# IR.net
KiCad netlist of a schematic drawn in EAGLE
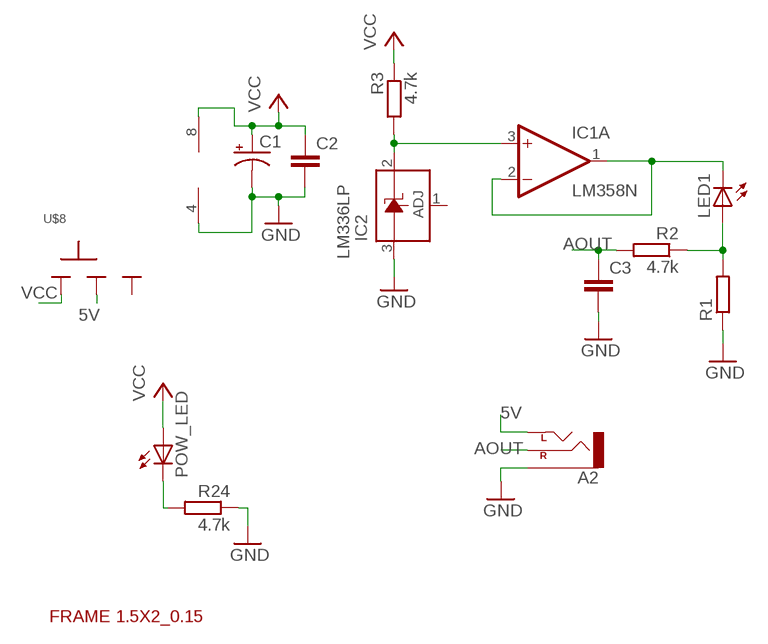
[diagram p0: schematic, sheet 1]

(export (version "E")
  (design (tool "Eeschema 10.0.6"))
  (components
    (comp (ref "A2")
      (value "AUX-CONNECTOR_CEDT_JANUARY_2015_V5_AUDIO-JACKPTH")
      (footprint "eagle-import:AUX-CONNECTOR_CEDT_JANUARY_2015_V5_AUDIO-JACK")
      (libsource (lib "eagle-import") (part "AUX-CONNECTOR_CEDT_JANUARY_2015_V5_AUDIO-JACKPTH"))
    )
    (comp (ref "C1")
      (value "CAP_POL")
      (footprint "eagle-import:E2,5-5-10U")
      (libsource (lib "eagle-import") (part "CAP_POL"))
    )
    (comp (ref "C2")
      (value "C-EU025-024X044")
      (footprint "eagle-import:C025-024X044")
      (libsource (lib "eagle-import") (part "C-EU025-024X044"))
    )
    (comp (ref "C3")
      (value "C-EU025-024X044")
      (footprint "eagle-import:C025-024X044")
      (libsource (lib "eagle-import") (part "C-EU025-024X044"))
    )
    (comp (ref "IC1")
      (value "LM358N")
      (footprint "eagle-import:DIL08")
      (libsource (lib "eagle-import") (part "LM358N"))
    )
    (comp (ref "IC2")
      (value "LM336LP")
      (footprint "eagle-import:TO92")
      (libsource (lib "eagle-import") (part "LM336LP"))
    )
    (comp (ref "LED1")
      (value "LED5MM")
      (footprint "eagle-import:LED5MM")
      (libsource (lib "eagle-import") (part "LED5MM"))
    )
    (comp (ref "POW_LED")
      (value "LED3MM")
      (footprint "eagle-import:LED3MM")
      (libsource (lib "eagle-import") (part "LED3MM"))
    )
    (comp (ref "R1")
      (value "R-EU_0204/7")
      (footprint "eagle-import:0204_7")
      (libsource (lib "eagle-import") (part "resistor_348_R-EU_0204/7"))
    )
    (comp (ref "R2")
      (value "4.7k")
      (footprint "eagle-import:0204_7")
      (libsource (lib "eagle-import") (part "R-EU_0204/7"))
    )
    (comp (ref "R3")
      (value "4.7k")
      (footprint "eagle-import:0204_7")
      (libsource (lib "eagle-import") (part "R-EU_0204/7"))
    )
    (comp (ref "R24")
      (value "4.7k")
      (footprint "eagle-import:0204_7")
      (libsource (lib "eagle-import") (part "R-EU_0204/7"))
    )
    (comp (ref "U$1")
      (value "FRAME_1.5X2_RAD_0.15")
      (footprint "eagle-import:FRAME_1.5X2_RAD_0.15")
      (libsource (lib "eagle-import") (part "FRAME_1.5X2_RAD_0.15"))
    )
    (comp (ref "U$8")
      (value "SLIDESWITCH-BIG")
      (footprint "eagle-import:BIGSWITCH")
      (libsource (lib "eagle-import") (part "SLIDESWITCH-BIG"))
    )
  )
  (nets
    (net (code "1") (name "/5V") (class "Default")
      (node (ref "A2") (pin "TIP") (pinfunction "LEFT_TIP") (pintype "bidirectional"))
      (node (ref "U$8") (pin "2") (pinfunction "2_2") (pintype "bidirectional"))
    )
    (net (code "2") (name "/AOUT") (class "Default")
      (node (ref "A2") (pin "RING") (pinfunction "RIGHT_RING") (pintype "bidirectional"))
      (node (ref "C3") (pin "1") (pinfunction "1_1") (pintype "passive"))
      (node (ref "R2") (pin "2") (pinfunction "2_2") (pintype "passive"))
    )
    (net (code "3") (name "GND") (class "Default")
      (node (ref "A2") (pin "SLEEVE") (pinfunction "SLEEVE_SLEEVE") (pintype "bidirectional"))
      (node (ref "C1") (pin "-") (pinfunction "-_-") (pintype "passive"))
      (node (ref "C2") (pin "2") (pinfunction "2_2") (pintype "passive"))
      (node (ref "C3") (pin "2") (pinfunction "2_2") (pintype "passive"))
      (node (ref "IC1") (pin "4") (pinfunction "V-_4") (pintype "power_in"))
      (node (ref "IC2") (pin "3") (pinfunction "A_3") (pintype "input"))
      (node (ref "R1") (pin "1") (pinfunction "1_1") (pintype "passive"))
      (node (ref "R24") (pin "1") (pinfunction "1_1") (pintype "passive"))
    )
    (net (code "4") (name "Net-(IC1A-+IN)") (class "Default")
      (node (ref "IC1") (pin "3") (pinfunction "+IN_3") (pintype "input"))
      (node (ref "IC2") (pin "2") (pinfunction "C_2") (pintype "passive"))
      (node (ref "R3") (pin "2") (pinfunction "2_2") (pintype "passive"))
    )
    (net (code "5") (name "Net-(IC1A--IN)") (class "Default")
      (node (ref "IC1") (pin "1") (pinfunction "OUT_1") (pintype "output"))
      (node (ref "IC1") (pin "2") (pinfunction "-IN_2") (pintype "input"))
      (node (ref "LED1") (pin "K") (pinfunction "C_K") (pintype "passive"))
    )
    (net (code "6") (name "Net-(LED1-PadA)") (class "Default")
      (node (ref "LED1") (pin "A") (pinfunction "A_A") (pintype "passive"))
      (node (ref "R1") (pin "2") (pinfunction "2_2") (pintype "passive"))
      (node (ref "R2") (pin "1") (pinfunction "1_1") (pintype "passive"))
    )
    (net (code "7") (name "Net-(POW_LED-C)") (class "Default")
      (node (ref "POW_LED") (pin "K") (pinfunction "C_K") (pintype "passive"))
      (node (ref "R24") (pin "2") (pinfunction "2_2") (pintype "passive"))
    )
    (net (code "8") (name "VCC") (class "Default")
      (node (ref "C1") (pin "+") (pinfunction "+_+") (pintype "passive"))
      (node (ref "C2") (pin "1") (pinfunction "1_1") (pintype "passive"))
      (node (ref "IC1") (pin "8") (pinfunction "V+_8") (pintype "power_in"))
      (node (ref "POW_LED") (pin "A") (pinfunction "A_A") (pintype "passive"))
      (node (ref "R3") (pin "1") (pinfunction "1_1") (pintype "passive"))
      (node (ref "U$8") (pin "1") (pinfunction "1_1") (pintype "bidirectional"))
    )
    (net (code "9") (name "unconnected-(IC2-ADJ-Pad1)") (class "Default")
      (node (ref "IC2") (pin "1") (pinfunction "ADJ_1") (pintype "input"))
    )
    (net (code "10") (name "unconnected-(U$8-Pad3)") (class "Default")
      (node (ref "U$8") (pin "3") (pinfunction "3_3") (pintype "bidirectional"))
    )
  )
)
